# Pwr.net
KiCad netlist of a schematic drawn in Altium Designer
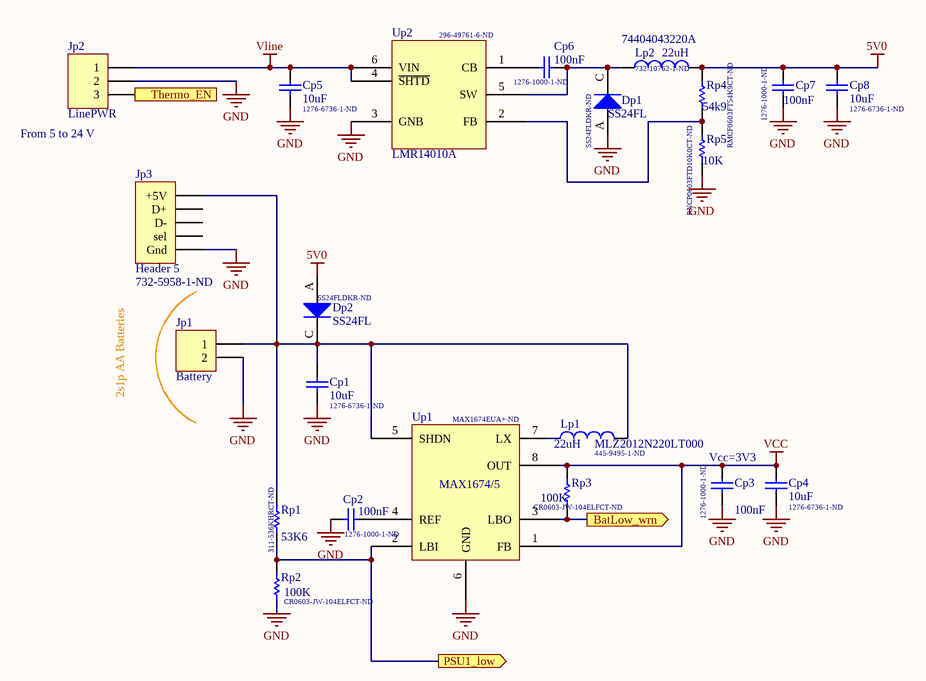
[diagram p0: Pwr.SchDoc]

(export (version "E")
  (design (tool "Eeschema 10.0.6"))
  (components
    (comp (ref "Cp1")
      (value "10uF")
      (footprint "C1206")
      (description "Capacitor")
      (fields
        (field (name "SUPPLIER PART NUMBER 1") "1276-6736-1-ND")
        (field (name "Comment") "Cap")
        (field (name "PUBLISHER") "Altium Limited")
      )
      (libsource (lib "Miscellaneous Devices") (part "Cap"))
    )
    (comp (ref "Cp2")
      (value "100nF")
      (footprint "c0603")
      (description "Capacitor")
      (fields
        (field (name "SUPPLIER PART NUMBER 1") "1276-1000-1-ND")
        (field (name "Comment") "Cap")
        (field (name "PUBLISHER") "Altium Limited")
      )
      (libsource (lib "Miscellaneous Devices") (part "Cap"))
    )
    (comp (ref "Cp3")
      (value "100nF")
      (footprint "c0603")
      (description "Capacitor")
      (fields
        (field (name "SUPPLIER PART NUMBER 1") "1276-1000-1-ND")
        (field (name "Comment") "Cap")
        (field (name "PUBLISHER") "Altium Limited")
      )
      (libsource (lib "Miscellaneous Devices") (part "Cap"))
    )
    (comp (ref "Cp4")
      (value "10uF")
      (footprint "C1206")
      (description "Capacitor")
      (fields
        (field (name "SUPPLIER PART NUMBER 1") "1276-6736-1-ND")
        (field (name "Comment") "Cap")
        (field (name "PUBLISHER") "Altium Limited")
      )
      (libsource (lib "Miscellaneous Devices") (part "Cap"))
    )
    (comp (ref "Cp5")
      (value "10uF")
      (footprint "C1206")
      (description "Capacitor")
      (fields
        (field (name "SUPPLIER PART NUMBER 1") "1276-6736-1-ND")
        (field (name "Comment") "Cap")
        (field (name "PUBLISHER") "Altium Limited")
      )
      (libsource (lib "Miscellaneous Devices") (part "Cap"))
    )
    (comp (ref "Cp6")
      (value "100nF")
      (footprint "c0603")
      (description "Capacitor")
      (fields
        (field (name "SUPPLIER PART NUMBER 1") "1276-1000-1-ND")
        (field (name "Comment") "Cap")
        (field (name "PUBLISHER") "Altium Limited")
      )
      (libsource (lib "Miscellaneous Devices") (part "Cap"))
    )
    (comp (ref "Cp7")
      (value "100nF")
      (footprint "c0603")
      (description "Capacitor")
      (fields
        (field (name "SUPPLIER PART NUMBER 1") "1276-1000-1-ND")
        (field (name "Comment") "Cap")
        (field (name "PUBLISHER") "Altium Limited")
      )
      (libsource (lib "Miscellaneous Devices") (part "Cap"))
    )
    (comp (ref "Cp8")
      (value "10uF")
      (footprint "C1206")
      (description "Capacitor")
      (fields
        (field (name "SUPPLIER PART NUMBER 1") "1276-6736-1-ND")
        (field (name "Comment") "Cap")
        (field (name "PUBLISHER") "Altium Limited")
      )
      (libsource (lib "Miscellaneous Devices") (part "Cap"))
    )
    (comp (ref "Dp1")
      (value "SS24FL")
      (footprint "SOD123F")
      (description "Default Diode")
      (fields
        (field (name "SUPPLIER PART NUMBER 1") "SS24FLDKR-ND")
        (field (name "PUBLISHER") "Altium Limited")
      )
      (libsource (lib "Miscellaneous Devices") (part "Diode"))
    )
    (comp (ref "Dp2")
      (value "SS24FL")
      (footprint "SOD123F")
      (description "Default Diode")
      (fields
        (field (name "SUPPLIER PART NUMBER 1") "SS24FLDKR-ND")
        (field (name "PUBLISHER") "Altium Limited")
      )
      (libsource (lib "Miscellaneous Devices") (part "Diode"))
    )
    (comp (ref "Jp1")
      (value "Battery")
      (footprint "HDR1X2")
      (description "Header, 2-Pin")
      (fields (field (name "PUBLISHER") "Altium Limited"))
      (libsource (lib "Miscellaneous Connectors") (part "Header 2"))
    )
    (comp (ref "Jp2")
      (value "LinePWR")
      (footprint "HDR1X3")
      (description "Header, 3-Pin")
      (fields (field (name "PUBLISHER") "Altium Limited"))
      (libsource (lib "Miscellaneous Connectors") (part "Header 3"))
    )
    (comp (ref "Jp3")
      (value "Header 5")
      (footprint "614105150721")
      (description "Header, 5-Pin")
      (fields
        (field (name "SUPPLIER PART NUMBER 1") "732-5958-1-ND")
        (field (name "PUBLISHER") "Altium Limited")
      )
      (libsource (lib "Miscellaneous Connectors") (part "Header 5"))
    )
    (comp (ref "Lp1")
      (value "MLZ2012N220LT000")
      (footprint "6-0805_L")
      (description "Inductor")
      (fields
        (field (name "ALTIUM_VALUE") "22uH")
        (field (name "SUPPLIER PART NUMBER 1") "445-9495-1-ND")
        (field (name "PUBLISHER") "Altium Limited")
      )
      (libsource (lib "Miscellaneous Devices") (part "Inductor"))
    )
    (comp (ref "Lp2")
      (value "74404043220A")
      (footprint "WE_ind_4x4")
      (description "Inductor")
      (fields
        (field (name "ALTIUM_VALUE") "22uH")
        (field (name "SUPPLIER PART NUMBER 1") "732-10762-1-ND")
        (field (name "PUBLISHER") "Altium Limited")
      )
      (libsource (lib "Miscellaneous Devices") (part "Inductor"))
    )
    (comp (ref "Rp1")
      (value "53K6")
      (footprint "r0603")
      (description "Resistor")
      (fields
        (field (name "SUPPLIER PART NUMBER 1") "311-536KHRCT-ND")
        (field (name "Comment") "Res1")
        (field (name "PUBLISHER") "Altium Limited")
      )
      (libsource (lib "Miscellaneous Devices") (part "Res1"))
    )
    (comp (ref "Rp2")
      (value "100K")
      (footprint "r0603")
      (description "Resistor")
      (fields
        (field (name "SUPPLIER PART NUMBER 1") "CR0603-JW-104ELFCT-ND")
        (field (name "Comment") "Res1")
        (field (name "PUBLISHER") "Altium Limited")
      )
      (libsource (lib "Miscellaneous Devices") (part "Res1"))
    )
    (comp (ref "Rp3")
      (value "100K")
      (footprint "r0603")
      (description "Resistor")
      (fields
        (field (name "SUPPLIER PART NUMBER 1") "CR0603-JW-104ELFCT-ND")
        (field (name "Comment") "Res1")
        (field (name "PUBLISHER") "Altium Limited")
      )
      (libsource (lib "Miscellaneous Devices") (part "Res1"))
    )
    (comp (ref "Rp4")
      (value "54k9")
      (footprint "r0603")
      (description "Resistor")
      (fields
        (field (name "SUPPLIER PART NUMBER 1") "RMCF0603FT54K9CT-ND")
        (field (name "Comment") "Res1")
        (field (name "PUBLISHER") "Altium Limited")
      )
      (libsource (lib "Miscellaneous Devices") (part "Res1"))
    )
    (comp (ref "Rp5")
      (value "10K")
      (footprint "r0603")
      (description "Resistor")
      (fields
        (field (name "SUPPLIER PART NUMBER 1") "RNCP0603FTD10K0CT-ND")
        (field (name "Comment") "Res1")
        (field (name "PUBLISHER") "Altium Limited")
      )
      (libsource (lib "Miscellaneous Devices") (part "Res1"))
    )
    (comp (ref "Up1")
      (value "MAX1674/5")
      (footprint "MSOP-8_TermalPad")
      (description "High-Efficiency, Low-Supply-Current,\r\nCompact, Step-Up DC-DC Converters")
      (fields (field (name "SUPPLIER PART NUMBER 1") "MAX1674EUA+-ND"))
      (libsource (lib "Maxim") (part "MAX1674/5"))
    )
    (comp (ref "Up2")
      (value "LMR14010A")
      (footprint "SOT23-6")
      (description "LMR14010A 4-V to 40-V, 1-A Step-Down Converter With High Efficiency Eco-mode")
      (fields (field (name "SUPPLIER PART NUMBER 1") "296-49761-6-ND"))
      (libsource (lib "TexasInstruments") (part "LMR14010A"))
    )
  )
  (nets
    (net (code "1") (name "/BatLow_wrn") (class "Default")
      (node (ref "Rp3") (pin "1") (pinfunction "1_1") (pintype "passive"))
      (node (ref "Up1") (pin "3") (pinfunction "LBO_3") (pintype "passive"))
    )
    (net (code "2") (name "/PSU1_low") (class "Default")
      (node (ref "Rp1") (pin "1") (pinfunction "1_1") (pintype "passive"))
      (node (ref "Rp2") (pin "2") (pinfunction "2_2") (pintype "passive"))
      (node (ref "Up1") (pin "2") (pinfunction "LBI_2") (pintype "passive"))
    )
    (net (code "3") (name "/Thermo_EN") (class "Default")
      (node (ref "Jp2") (pin "3") (pinfunction "3_3") (pintype "passive"))
    )
    (net (code "4") (name "5V0") (class "Default")
      (node (ref "Cp7") (pin "1") (pinfunction "1_1") (pintype "passive"))
      (node (ref "Cp8") (pin "2") (pinfunction "2_2") (pintype "passive"))
      (node (ref "Dp2") (pin "A") (pinfunction "A_A") (pintype "passive"))
      (node (ref "Lp2") (pin "2") (pinfunction "2_2") (pintype "passive"))
      (node (ref "Rp4") (pin "2") (pinfunction "2_2") (pintype "passive"))
    )
    (net (code "5") (name "GND") (class "Default")
      (node (ref "Cp1") (pin "1") (pinfunction "1_1") (pintype "passive"))
      (node (ref "Cp2") (pin "2") (pinfunction "2_2") (pintype "passive"))
      (node (ref "Cp3") (pin "2") (pinfunction "2_2") (pintype "passive"))
      (node (ref "Cp4") (pin "1") (pinfunction "1_1") (pintype "passive"))
      (node (ref "Cp5") (pin "1") (pinfunction "1_1") (pintype "passive"))
      (node (ref "Cp7") (pin "2") (pinfunction "2_2") (pintype "passive"))
      (node (ref "Cp8") (pin "1") (pinfunction "1_1") (pintype "passive"))
      (node (ref "Dp1") (pin "A") (pinfunction "A_A") (pintype "passive"))
      (node (ref "Jp1") (pin "2") (pinfunction "2_2") (pintype "passive"))
      (node (ref "Jp2") (pin "2") (pinfunction "2_2") (pintype "passive"))
      (node (ref "Jp3") (pin "1") (pinfunction "Gnd_1") (pintype "passive"))
      (node (ref "Rp2") (pin "1") (pinfunction "1_1") (pintype "passive"))
      (node (ref "Rp5") (pin "1") (pinfunction "1_1") (pintype "passive"))
      (node (ref "Up1") (pin "6") (pinfunction "GND_6") (pintype "passive"))
      (node (ref "Up2") (pin "3") (pinfunction "GNB_3") (pintype "passive"))
    )
    (net (code "6") (name "Net-(Dp1-K)") (class "Default")
      (node (ref "Cp6") (pin "2") (pinfunction "2_2") (pintype "passive"))
      (node (ref "Dp1") (pin "C") (pinfunction "K_C") (pintype "passive"))
      (node (ref "Lp2") (pin "1") (pinfunction "1_1") (pintype "passive"))
      (node (ref "Up2") (pin "5") (pinfunction "SW_5") (pintype "passive"))
    )
    (net (code "7") (name "Net-(Dp2-K)") (class "Default")
      (node (ref "Cp1") (pin "2") (pinfunction "2_2") (pintype "passive"))
      (node (ref "Dp2") (pin "C") (pinfunction "K_C") (pintype "passive"))
      (node (ref "Jp1") (pin "1") (pinfunction "1_1") (pintype "passive"))
      (node (ref "Jp3") (pin "5") (pinfunction "+5V_5") (pintype "passive"))
      (node (ref "Lp1") (pin "2") (pinfunction "2_2") (pintype "passive"))
      (node (ref "Rp1") (pin "2") (pinfunction "2_2") (pintype "passive"))
      (node (ref "Up1") (pin "5") (pinfunction "SHDN_5") (pintype "passive"))
    )
    (net (code "8") (name "Net-(Up1-LX)") (class "Default")
      (node (ref "Lp1") (pin "1") (pinfunction "1_1") (pintype "passive"))
      (node (ref "Up1") (pin "7") (pinfunction "LX_7") (pintype "passive"))
    )
    (net (code "9") (name "Net-(Up1-REF)") (class "Default")
      (node (ref "Cp2") (pin "1") (pinfunction "1_1") (pintype "passive"))
      (node (ref "Up1") (pin "4") (pinfunction "REF_4") (pintype "passive"))
    )
    (net (code "10") (name "Net-(Up2-CB)") (class "Default")
      (node (ref "Cp6") (pin "1") (pinfunction "1_1") (pintype "passive"))
      (node (ref "Up2") (pin "1") (pinfunction "CB_1") (pintype "passive"))
    )
    (net (code "11") (name "Net-(Up2-FB)") (class "Default")
      (node (ref "Rp4") (pin "1") (pinfunction "1_1") (pintype "passive"))
      (node (ref "Rp5") (pin "2") (pinfunction "2_2") (pintype "passive"))
      (node (ref "Up2") (pin "2") (pinfunction "FB_2") (pintype "passive"))
    )
    (net (code "12") (name "VCC") (class "Default")
      (node (ref "Cp3") (pin "1") (pinfunction "1_1") (pintype "passive"))
      (node (ref "Cp4") (pin "2") (pinfunction "2_2") (pintype "passive"))
      (node (ref "Rp3") (pin "2") (pinfunction "2_2") (pintype "passive"))
      (node (ref "Up1") (pin "1") (pinfunction "FB_1") (pintype "passive"))
      (node (ref "Up1") (pin "8") (pinfunction "OUT_8") (pintype "passive"))
    )
    (net (code "13") (name "Vline") (class "Default")
      (node (ref "Cp5") (pin "2") (pinfunction "2_2") (pintype "passive"))
      (node (ref "Jp2") (pin "1") (pinfunction "1_1") (pintype "passive"))
      (node (ref "Up2") (pin "4") (pinfunction "~{SHTD}_4") (pintype "passive"))
      (node (ref "Up2") (pin "6") (pinfunction "VIN_6") (pintype "passive"))
    )
    (net (code "14") (name "unconnected-(Jp3-D+-Pad4)") (class "Default")
      (node (ref "Jp3") (pin "4") (pinfunction "D+_4") (pintype "passive"))
    )
    (net (code "15") (name "unconnected-(Jp3-D--Pad3)") (class "Default")
      (node (ref "Jp3") (pin "3") (pinfunction "D-_3") (pintype "passive"))
    )
    (net (code "16") (name "unconnected-(Jp3-sel-Pad2)") (class "Default")
      (node (ref "Jp3") (pin "2") (pinfunction "sel_2") (pintype "passive"))
    )
  )
)
